# Sheet1.net
KiCad netlist of a schematic drawn in Altium Designer
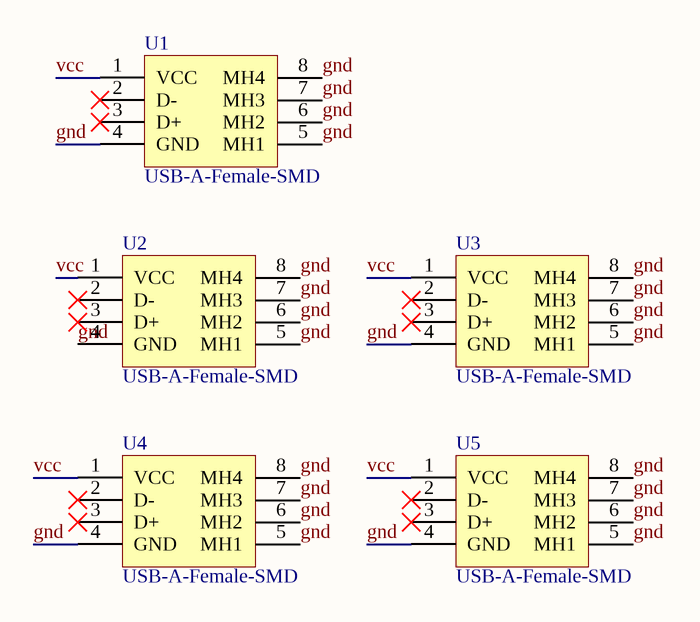
[diagram p0: Sheet1.SchDoc]

(export (version "E")
  (design (tool "Eeschema 10.0.6"))
  (components
    (comp (ref "U1")
      (value "USB-A-Female-SMD")
      (footprint "USB-A-SMD")
      (libsource (lib "Vowstar_Connector") (part "USB-A-Female-SMD"))
    )
    (comp (ref "U2")
      (value "USB-A-Female-SMD")
      (footprint "USB-A-SMD")
      (libsource (lib "Vowstar_Connector") (part "USB-A-Female-SMD"))
    )
    (comp (ref "U3")
      (value "USB-A-Female-SMD")
      (footprint "USB-A-SMD")
      (libsource (lib "Vowstar_Connector") (part "USB-A-Female-SMD"))
    )
    (comp (ref "U4")
      (value "USB-A-Female-SMD")
      (footprint "USB-A-SMD")
      (libsource (lib "Vowstar_Connector") (part "USB-A-Female-SMD"))
    )
    (comp (ref "U5")
      (value "USB-A-Female-SMD")
      (footprint "USB-A-SMD")
      (libsource (lib "Vowstar_Connector") (part "USB-A-Female-SMD"))
    )
  )
  (nets
    (net (code "1") (name "/gnd") (class "Default")
      (node (ref "U1") (pin "4") (pinfunction "GND_4") (pintype "passive"))
      (node (ref "U1") (pin "5") (pinfunction "MH1_5") (pintype "passive"))
      (node (ref "U1") (pin "6") (pinfunction "MH2_6") (pintype "passive"))
      (node (ref "U1") (pin "7") (pinfunction "MH3_7") (pintype "passive"))
      (node (ref "U1") (pin "8") (pinfunction "MH4_8") (pintype "passive"))
      (node (ref "U2") (pin "4") (pinfunction "GND_4") (pintype "passive"))
      (node (ref "U2") (pin "5") (pinfunction "MH1_5") (pintype "passive"))
      (node (ref "U2") (pin "6") (pinfunction "MH2_6") (pintype "passive"))
      (node (ref "U2") (pin "7") (pinfunction "MH3_7") (pintype "passive"))
      (node (ref "U2") (pin "8") (pinfunction "MH4_8") (pintype "passive"))
      (node (ref "U3") (pin "4") (pinfunction "GND_4") (pintype "passive"))
      (node (ref "U3") (pin "5") (pinfunction "MH1_5") (pintype "passive"))
      (node (ref "U3") (pin "6") (pinfunction "MH2_6") (pintype "passive"))
      (node (ref "U3") (pin "7") (pinfunction "MH3_7") (pintype "passive"))
      (node (ref "U3") (pin "8") (pinfunction "MH4_8") (pintype "passive"))
      (node (ref "U4") (pin "4") (pinfunction "GND_4") (pintype "passive"))
      (node (ref "U4") (pin "5") (pinfunction "MH1_5") (pintype "passive"))
      (node (ref "U4") (pin "6") (pinfunction "MH2_6") (pintype "passive"))
      (node (ref "U4") (pin "7") (pinfunction "MH3_7") (pintype "passive"))
      (node (ref "U4") (pin "8") (pinfunction "MH4_8") (pintype "passive"))
      (node (ref "U5") (pin "4") (pinfunction "GND_4") (pintype "passive"))
      (node (ref "U5") (pin "5") (pinfunction "MH1_5") (pintype "passive"))
      (node (ref "U5") (pin "6") (pinfunction "MH2_6") (pintype "passive"))
      (node (ref "U5") (pin "7") (pinfunction "MH3_7") (pintype "passive"))
      (node (ref "U5") (pin "8") (pinfunction "MH4_8") (pintype "passive"))
    )
    (net (code "2") (name "/vcc") (class "Default")
      (node (ref "U1") (pin "1") (pinfunction "VCC_1") (pintype "passive"))
      (node (ref "U2") (pin "1") (pinfunction "VCC_1") (pintype "passive"))
      (node (ref "U3") (pin "1") (pinfunction "VCC_1") (pintype "passive"))
      (node (ref "U4") (pin "1") (pinfunction "VCC_1") (pintype "passive"))
      (node (ref "U5") (pin "1") (pinfunction "VCC_1") (pintype "passive"))
    )
    (net (code "3") (name "unconnected-(U1-D+-Pad3)") (class "Default")
      (node (ref "U1") (pin "3") (pinfunction "D+_3") (pintype "passive+no_connect"))
    )
    (net (code "4") (name "unconnected-(U1-D--Pad2)") (class "Default")
      (node (ref "U1") (pin "2") (pinfunction "D-_2") (pintype "passive+no_connect"))
    )
    (net (code "5") (name "unconnected-(U2-D+-Pad3)") (class "Default")
      (node (ref "U2") (pin "3") (pinfunction "D+_3") (pintype "passive+no_connect"))
    )
    (net (code "6") (name "unconnected-(U2-D--Pad2)") (class "Default")
      (node (ref "U2") (pin "2") (pinfunction "D-_2") (pintype "passive+no_connect"))
    )
    (net (code "7") (name "unconnected-(U3-D+-Pad3)") (class "Default")
      (node (ref "U3") (pin "3") (pinfunction "D+_3") (pintype "passive+no_connect"))
    )
    (net (code "8") (name "unconnected-(U3-D--Pad2)") (class "Default")
      (node (ref "U3") (pin "2") (pinfunction "D-_2") (pintype "passive+no_connect"))
    )
    (net (code "9") (name "unconnected-(U4-D+-Pad3)") (class "Default")
      (node (ref "U4") (pin "3") (pinfunction "D+_3") (pintype "passive+no_connect"))
    )
    (net (code "10") (name "unconnected-(U4-D--Pad2)") (class "Default")
      (node (ref "U4") (pin "2") (pinfunction "D-_2") (pintype "passive+no_connect"))
    )
    (net (code "11") (name "unconnected-(U5-D+-Pad3)") (class "Default")
      (node (ref "U5") (pin "3") (pinfunction "D+_3") (pintype "passive+no_connect"))
    )
    (net (code "12") (name "unconnected-(U5-D--Pad2)") (class "Default")
      (node (ref "U5") (pin "2") (pinfunction "D-_2") (pintype "passive+no_connect"))
    )
  )
)
